# jayday.net
KiCad netlist of a schematic drawn in EAGLE
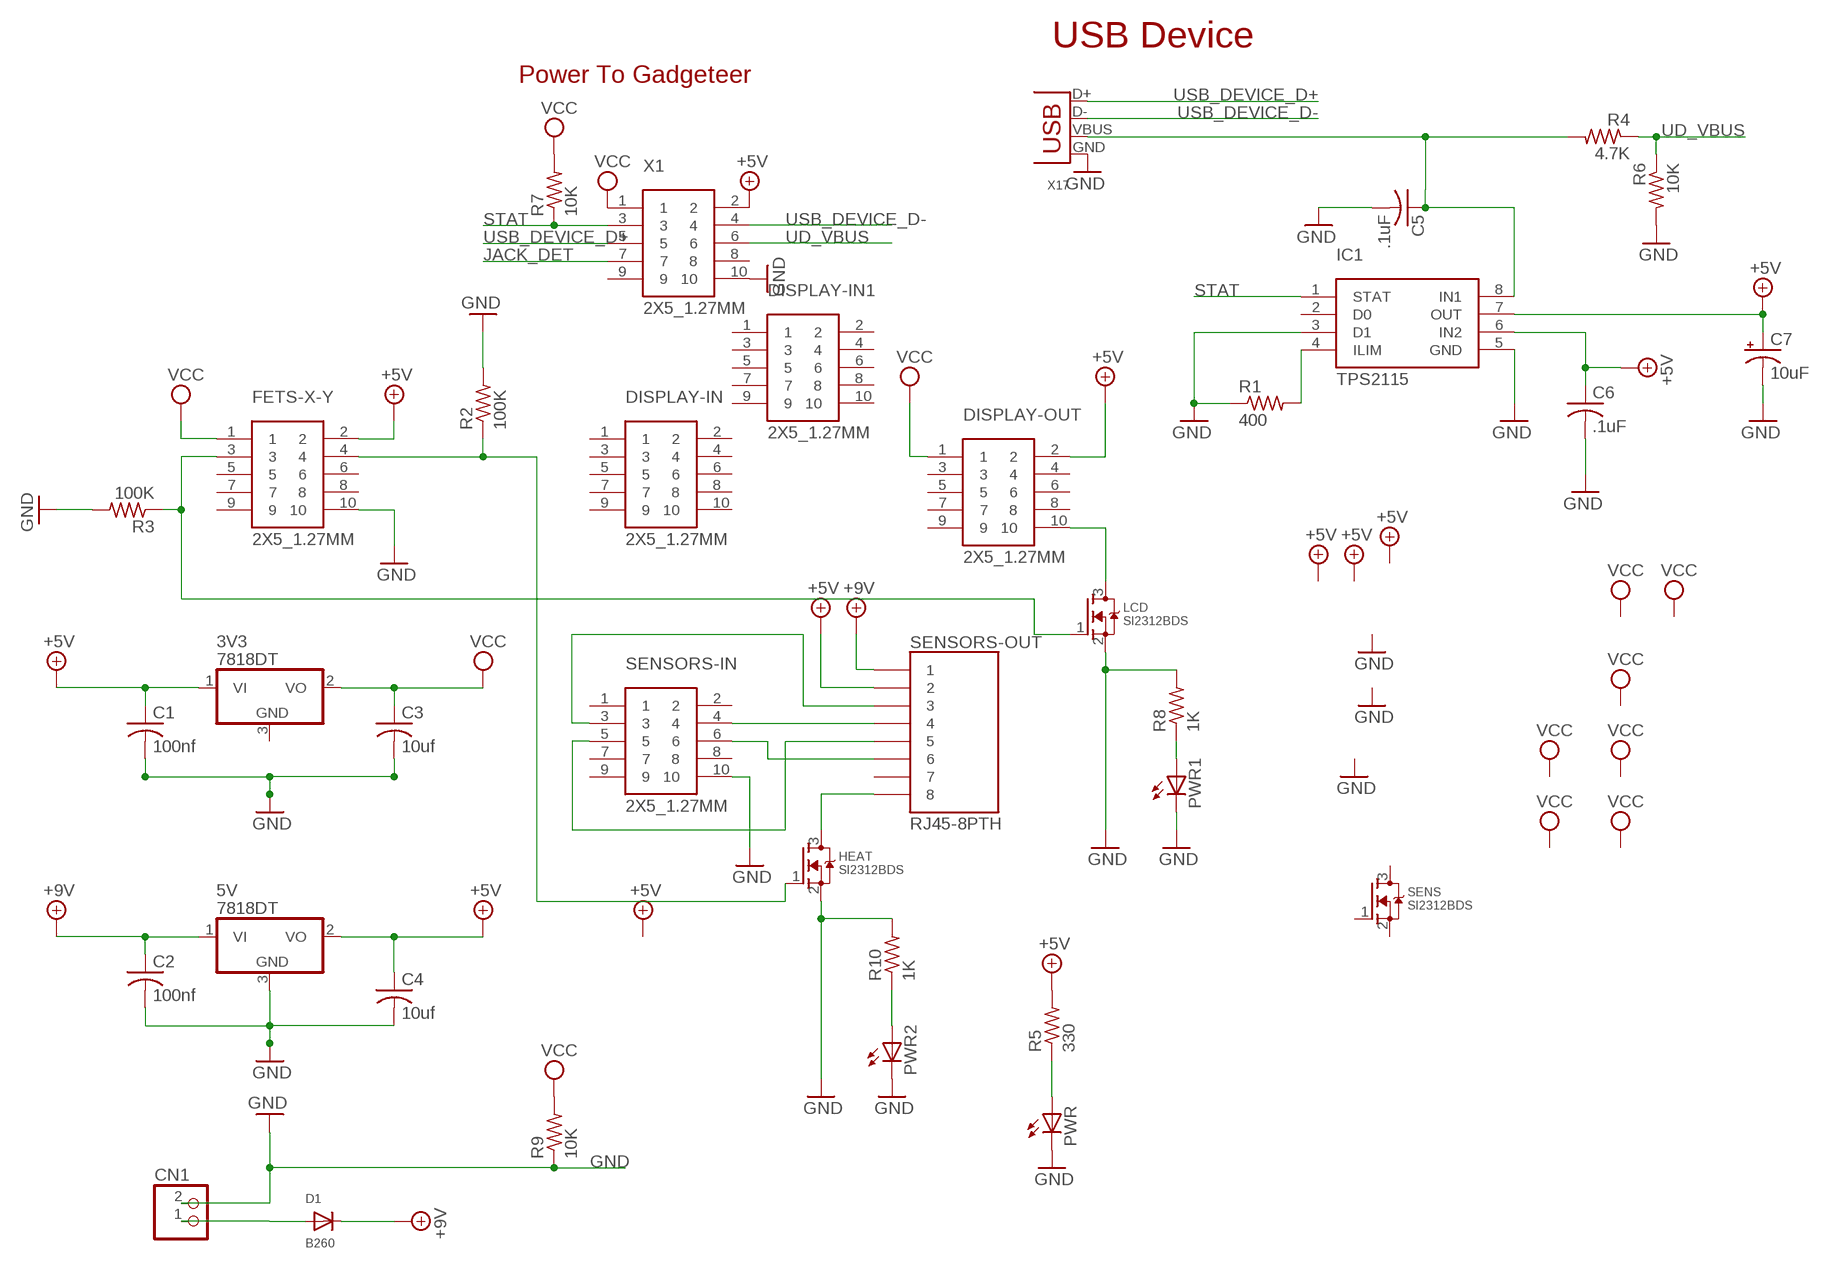
[diagram p0: schematic, sheet 1]

(export (version "E")
  (design (tool "Eeschema 10.0.6"))
  (components
    (comp (ref "3V3")
      (value "7818DT")
      (footprint "eagle-import:TO252")
      (libsource (lib "eagle-import") (part "78DT18"))
    )
    (comp (ref "5V")
      (value "7818DT")
      (footprint "eagle-import:TO252")
      (libsource (lib "eagle-import") (part "78DT18"))
    )
    (comp (ref "C1")
      (value "100nf")
      (footprint "eagle-import:C0805")
      (libsource (lib "eagle-import") (part "C-USC0805"))
    )
    (comp (ref "C2")
      (value "100nf")
      (footprint "eagle-import:C0805")
      (libsource (lib "eagle-import") (part "C-USC0805"))
    )
    (comp (ref "C3")
      (value "10uf")
      (footprint "eagle-import:C0805")
      (libsource (lib "eagle-import") (part "C-USC0805"))
    )
    (comp (ref "C4")
      (value "10uf")
      (footprint "eagle-import:C0805")
      (libsource (lib "eagle-import") (part "C-USC0805"))
    )
    (comp (ref "C5")
      (value ".1uF")
      (footprint "eagle-import:C0603K")
      (libsource (lib "eagle-import") (part "rcl_C-USC0603K"))
    )
    (comp (ref "C6")
      (value ".1uF")
      (footprint "eagle-import:C0603K")
      (libsource (lib "eagle-import") (part "rcl_C-USC0603K"))
    )
    (comp (ref "C7")
      (value "10uF")
      (footprint "eagle-import:CT3528")
      (libsource (lib "eagle-import") (part "CPOL-USCT3528"))
    )
    (comp (ref "CN1")
      (value "JST_2PIN-THM-RA")
      (footprint "eagle-import:JST-PH-2-THM-RA")
      (libsource (lib "eagle-import") (part "JST_2PIN-THM-RA"))
    )
    (comp (ref "D1")
      (value "B260")
      (footprint "eagle-import:SMADIODE")
      (libsource (lib "eagle-import") (part "DIODESMA"))
    )
    (comp (ref "DISPLAY-IN")
      (value "2X5_1.27MM")
      (footprint "eagle-import:2X5_1.27MM")
      (libsource (lib "eagle-import") (part "2X5_1.27MM"))
    )
    (comp (ref "DISPLAY-IN1")
      (value "2X5_1.27MM")
      (footprint "eagle-import:2X5_1.27MM")
      (libsource (lib "eagle-import") (part "2X5_1.27MM"))
    )
    (comp (ref "DISPLAY-OUT")
      (value "2X5_1.27MM")
      (footprint "eagle-import:2X5_1.27MM")
      (libsource (lib "eagle-import") (part "2X5_1.27MM"))
    )
    (comp (ref "FETS-X-Y")
      (value "2X5_1.27MM")
      (footprint "eagle-import:2X5_1.27MM")
      (libsource (lib "eagle-import") (part "2X5_1.27MM"))
    )
    (comp (ref "HEAT")
      (value "SI2312BDS")
      (footprint "eagle-import:TO-236")
      (libsource (lib "eagle-import") (part "SI2312BDS"))
    )
    (comp (ref "IC1")
      (value "TPS2115")
      (footprint "eagle-import:TSSOP8")
      (libsource (lib "eagle-import") (part "TSP2115"))
    )
    (comp (ref "LCD")
      (value "SI2312BDS")
      (footprint "eagle-import:TO-236")
      (libsource (lib "eagle-import") (part "SI2312BDS"))
    )
    (comp (ref "PWR")
      (value "LEDCHIPLED_0805")
      (footprint "eagle-import:CHIPLED_0805")
      (libsource (lib "eagle-import") (part "LEDCHIPLED_0805"))
    )
    (comp (ref "PWR1")
      (value "LEDCHIPLED_0805")
      (footprint "eagle-import:CHIPLED_0805")
      (libsource (lib "eagle-import") (part "LEDCHIPLED_0805"))
    )
    (comp (ref "PWR2")
      (value "LEDCHIPLED_0805")
      (footprint "eagle-import:CHIPLED_0805")
      (libsource (lib "eagle-import") (part "LEDCHIPLED_0805"))
    )
    (comp (ref "R1")
      (value "400")
      (footprint "eagle-import:R0603")
      (libsource (lib "eagle-import") (part "R-US_R0603"))
    )
    (comp (ref "R2")
      (value "100K")
      (footprint "eagle-import:R0603")
      (libsource (lib "eagle-import") (part "R-US_R0603"))
    )
    (comp (ref "R3")
      (value "100K")
      (footprint "eagle-import:R0603")
      (libsource (lib "eagle-import") (part "R-US_R0603"))
    )
    (comp (ref "R4")
      (value "4.7K")
      (footprint "eagle-import:R0603")
      (libsource (lib "eagle-import") (part "R-US_R0603"))
    )
    (comp (ref "R5")
      (value "330")
      (footprint "eagle-import:R0603")
      (libsource (lib "eagle-import") (part "R-US_R0603"))
    )
    (comp (ref "R6")
      (value "10K")
      (footprint "eagle-import:R0603")
      (libsource (lib "eagle-import") (part "R-US_R0603"))
    )
    (comp (ref "R7")
      (value "10K")
      (footprint "eagle-import:R0603")
      (libsource (lib "eagle-import") (part "R-US_R0603"))
    )
    (comp (ref "R8")
      (value "1K")
      (footprint "eagle-import:R0603")
      (libsource (lib "eagle-import") (part "R-US_R0603"))
    )
    (comp (ref "R9")
      (value "10K")
      (footprint "eagle-import:R0603")
      (libsource (lib "eagle-import") (part "R-US_R0603"))
    )
    (comp (ref "R10")
      (value "1K")
      (footprint "eagle-import:R0603")
      (libsource (lib "eagle-import") (part "R-US_R0603"))
    )
    (comp (ref "SENS")
      (value "SI2312BDS")
      (footprint "eagle-import:TO-236")
      (libsource (lib "eagle-import") (part "SI2312BDS"))
    )
    (comp (ref "SENSORS-IN")
      (value "2X5_1.27MM")
      (footprint "eagle-import:2X5_1.27MM")
      (libsource (lib "eagle-import") (part "2X5_1.27MM"))
    )
    (comp (ref "SENSORS-OUT")
      (value "RJ45-8PTH")
      (footprint "eagle-import:RJ45-8")
      (libsource (lib "eagle-import") (part "RJ45-8PTH"))
    )
    (comp (ref "X1")
      (value "2X5_1.27MM")
      (footprint "eagle-import:2X5_1.27MM")
      (libsource (lib "eagle-import") (part "2X5_1.27MM"))
    )
    (comp (ref "X17")
      (value "DX2R005HN2E700")
      (footprint "eagle-import:USB-MB-S")
      (libsource (lib "eagle-import") (part "USB-MB-S"))
    )
  )
  (nets
    (net (code "1") (name "+5V") (class "Default")
      (node (ref "3V3") (pin "1") (pinfunction "VI_1") (pintype "input"))
      (node (ref "5V") (pin "2") (pinfunction "VO_2") (pintype "passive"))
      (node (ref "C1") (pin "1") (pinfunction "1_1") (pintype "passive"))
      (node (ref "C4") (pin "1") (pinfunction "1_1") (pintype "passive"))
      (node (ref "C6") (pin "1") (pinfunction "1_1") (pintype "passive"))
      (node (ref "C7") (pin "+") (pinfunction "+_+") (pintype "passive"))
      (node (ref "DISPLAY-OUT") (pin "2") (pinfunction "2_2") (pintype "bidirectional"))
      (node (ref "FETS-X-Y") (pin "2") (pinfunction "2_2") (pintype "bidirectional"))
      (node (ref "IC1") (pin "6") (pinfunction "IN2_6") (pintype "bidirectional"))
      (node (ref "IC1") (pin "7") (pinfunction "OUT_7") (pintype "bidirectional"))
      (node (ref "R5") (pin "2") (pinfunction "2_2") (pintype "passive"))
      (node (ref "SENSORS-OUT") (pin "2") (pinfunction "2_2") (pintype "bidirectional"))
      (node (ref "X1") (pin "2") (pinfunction "2_2") (pintype "bidirectional"))
    )
    (net (code "2") (name "+9V") (class "Default")
      (node (ref "5V") (pin "1") (pinfunction "VI_1") (pintype "input"))
      (node (ref "C2") (pin "1") (pinfunction "1_1") (pintype "passive"))
      (node (ref "D1") (pin "C") (pinfunction "C_C") (pintype "passive"))
      (node (ref "SENSORS-OUT") (pin "1") (pinfunction "1_1") (pintype "bidirectional"))
    )
    (net (code "3") (name "/JACK_DET") (class "Default")
      (node (ref "X1") (pin "7") (pinfunction "7_7") (pintype "bidirectional"))
    )
    (net (code "4") (name "/STAT") (class "Default")
      (node (ref "IC1") (pin "1") (pinfunction "STAT_1") (pintype "bidirectional"))
      (node (ref "R7") (pin "1") (pinfunction "1_1") (pintype "passive"))
      (node (ref "X1") (pin "3") (pinfunction "3_3") (pintype "bidirectional"))
    )
    (net (code "5") (name "/UD_VBUS") (class "Default")
      (node (ref "R4") (pin "1") (pinfunction "1_1") (pintype "passive"))
      (node (ref "R6") (pin "1") (pinfunction "1_1") (pintype "passive"))
      (node (ref "X1") (pin "6") (pinfunction "6_6") (pintype "bidirectional"))
    )
    (net (code "6") (name "/USB_DEVICE_D+") (class "Default")
      (node (ref "X1") (pin "5") (pinfunction "5_5") (pintype "bidirectional"))
      (node (ref "X17") (pin "D+") (pinfunction "D+_D+") (pintype "bidirectional"))
    )
    (net (code "7") (name "/USB_DEVICE_D-") (class "Default")
      (node (ref "X1") (pin "4") (pinfunction "4_4") (pintype "bidirectional"))
      (node (ref "X17") (pin "D-") (pinfunction "D-_D-") (pintype "bidirectional"))
    )
    (net (code "8") (name "GND") (class "Default")
      (node (ref "5V") (pin "3") (pinfunction "GND_3") (pintype "passive"))
      (node (ref "C1") (pin "2") (pinfunction "2_2") (pintype "passive"))
      (node (ref "C2") (pin "2") (pinfunction "2_2") (pintype "passive"))
      (node (ref "C3") (pin "2") (pinfunction "2_2") (pintype "passive"))
      (node (ref "C4") (pin "2") (pinfunction "2_2") (pintype "passive"))
      (node (ref "C5") (pin "2") (pinfunction "2_2") (pintype "passive"))
      (node (ref "C6") (pin "2") (pinfunction "2_2") (pintype "passive"))
      (node (ref "C7") (pin "-") (pinfunction "-_-") (pintype "passive"))
      (node (ref "CN1") (pin "2") (pinfunction "1_2") (pintype "passive"))
      (node (ref "FETS-X-Y") (pin "10") (pinfunction "10_10") (pintype "bidirectional"))
      (node (ref "HEAT") (pin "2") (pinfunction "S_2") (pintype "bidirectional"))
      (node (ref "IC1") (pin "3") (pinfunction "D1_3") (pintype "bidirectional"))
      (node (ref "IC1") (pin "5") (pinfunction "GND_5") (pintype "bidirectional"))
      (node (ref "LCD") (pin "2") (pinfunction "S_2") (pintype "bidirectional"))
      (node (ref "PWR") (pin "C") (pinfunction "C_C") (pintype "passive"))
      (node (ref "PWR1") (pin "C") (pinfunction "C_C") (pintype "passive"))
      (node (ref "PWR2") (pin "C") (pinfunction "C_C") (pintype "passive"))
      (node (ref "R1") (pin "1") (pinfunction "1_1") (pintype "passive"))
      (node (ref "R10") (pin "2") (pinfunction "2_2") (pintype "passive"))
      (node (ref "R2") (pin "2") (pinfunction "2_2") (pintype "passive"))
      (node (ref "R3") (pin "2") (pinfunction "2_2") (pintype "passive"))
      (node (ref "R6") (pin "2") (pinfunction "2_2") (pintype "passive"))
      (node (ref "R8") (pin "2") (pinfunction "2_2") (pintype "passive"))
      (node (ref "R9") (pin "1") (pinfunction "1_1") (pintype "passive"))
      (node (ref "SENSORS-IN") (pin "10") (pinfunction "10_10") (pintype "bidirectional"))
      (node (ref "X1") (pin "10") (pinfunction "10_10") (pintype "bidirectional"))
      (node (ref "X17") (pin "GND") (pinfunction "GND_GND") (pintype "bidirectional"))
    )
    (net (code "9") (name "Net-(CN1-2)") (class "Default")
      (node (ref "CN1") (pin "1") (pinfunction "2_1") (pintype "passive"))
      (node (ref "D1") (pin "A") (pinfunction "A_A") (pintype "passive"))
    )
    (net (code "10") (name "Net-(HEAT-D)") (class "Default")
      (node (ref "HEAT") (pin "3") (pinfunction "D_3") (pintype "bidirectional"))
      (node (ref "SENSORS-OUT") (pin "8") (pinfunction "8_8") (pintype "bidirectional"))
    )
    (net (code "11") (name "Net-(HEAT-G)") (class "Default")
      (node (ref "FETS-X-Y") (pin "4") (pinfunction "4_4") (pintype "bidirectional"))
      (node (ref "HEAT") (pin "1") (pinfunction "G_1") (pintype "bidirectional"))
      (node (ref "R2") (pin "1") (pinfunction "1_1") (pintype "passive"))
    )
    (net (code "12") (name "Net-(IC1-ILIM)") (class "Default")
      (node (ref "IC1") (pin "4") (pinfunction "ILIM_4") (pintype "bidirectional"))
      (node (ref "R1") (pin "2") (pinfunction "2_2") (pintype "passive"))
    )
    (net (code "13") (name "Net-(IC1-IN1)") (class "Default")
      (node (ref "C5") (pin "1") (pinfunction "1_1") (pintype "passive"))
      (node (ref "IC1") (pin "8") (pinfunction "IN1_8") (pintype "bidirectional"))
      (node (ref "R4") (pin "2") (pinfunction "2_2") (pintype "passive"))
      (node (ref "X17") (pin "VBUS") (pinfunction "VBUS_VBUS") (pintype "bidirectional"))
    )
    (net (code "14") (name "Net-(LCD-D)") (class "Default")
      (node (ref "DISPLAY-OUT") (pin "10") (pinfunction "10_10") (pintype "bidirectional"))
      (node (ref "LCD") (pin "3") (pinfunction "D_3") (pintype "bidirectional"))
    )
    (net (code "15") (name "Net-(LCD-G)") (class "Default")
      (node (ref "FETS-X-Y") (pin "3") (pinfunction "3_3") (pintype "bidirectional"))
      (node (ref "LCD") (pin "1") (pinfunction "G_1") (pintype "bidirectional"))
      (node (ref "R3") (pin "1") (pinfunction "1_1") (pintype "passive"))
    )
    (net (code "16") (name "Net-(PWR-PadA)") (class "Default")
      (node (ref "PWR") (pin "A") (pinfunction "A_A") (pintype "passive"))
      (node (ref "R5") (pin "1") (pinfunction "1_1") (pintype "passive"))
    )
    (net (code "17") (name "Net-(PWR1-PadA)") (class "Default")
      (node (ref "PWR1") (pin "A") (pinfunction "A_A") (pintype "passive"))
      (node (ref "R8") (pin "1") (pinfunction "1_1") (pintype "passive"))
    )
    (net (code "18") (name "Net-(PWR2-PadA)") (class "Default")
      (node (ref "PWR2") (pin "A") (pinfunction "A_A") (pintype "passive"))
      (node (ref "R10") (pin "1") (pinfunction "1_1") (pintype "passive"))
    )
    (net (code "19") (name "Net-(SENSORS-IN-Pad3)") (class "Default")
      (node (ref "SENSORS-IN") (pin "3") (pinfunction "3_3") (pintype "bidirectional"))
      (node (ref "SENSORS-OUT") (pin "3") (pinfunction "3_3") (pintype "bidirectional"))
    )
    (net (code "20") (name "Net-(SENSORS-IN-Pad4)") (class "Default")
      (node (ref "SENSORS-IN") (pin "4") (pinfunction "4_4") (pintype "bidirectional"))
      (node (ref "SENSORS-OUT") (pin "4") (pinfunction "4_4") (pintype "bidirectional"))
    )
    (net (code "21") (name "Net-(SENSORS-IN-Pad5)") (class "Default")
      (node (ref "SENSORS-IN") (pin "5") (pinfunction "5_5") (pintype "bidirectional"))
      (node (ref "SENSORS-OUT") (pin "5") (pinfunction "5_5") (pintype "bidirectional"))
    )
    (net (code "22") (name "Net-(SENSORS-IN-Pad6)") (class "Default")
      (node (ref "SENSORS-IN") (pin "6") (pinfunction "6_6") (pintype "bidirectional"))
      (node (ref "SENSORS-OUT") (pin "6") (pinfunction "6_6") (pintype "bidirectional"))
    )
    (net (code "23") (name "VCC") (class "Default")
      (node (ref "3V3") (pin "2") (pinfunction "VO_2") (pintype "passive"))
      (node (ref "C3") (pin "1") (pinfunction "1_1") (pintype "passive"))
      (node (ref "DISPLAY-OUT") (pin "1") (pinfunction "1_1") (pintype "bidirectional"))
      (node (ref "FETS-X-Y") (pin "1") (pinfunction "1_1") (pintype "bidirectional"))
      (node (ref "R7") (pin "2") (pinfunction "2_2") (pintype "passive"))
      (node (ref "R9") (pin "2") (pinfunction "2_2") (pintype "passive"))
      (node (ref "X1") (pin "1") (pinfunction "1_1") (pintype "bidirectional"))
    )
    (net (code "24") (name "unconnected-(3V3-GND-Pad3)") (class "Default")
      (node (ref "3V3") (pin "3") (pinfunction "GND_3") (pintype "passive"))
    )
    (net (code "25") (name "unconnected-(DISPLAY-IN-Pad1)") (class "Default")
      (node (ref "DISPLAY-IN") (pin "1") (pinfunction "1_1") (pintype "bidirectional"))
    )
    (net (code "26") (name "unconnected-(DISPLAY-IN-Pad2)") (class "Default")
      (node (ref "DISPLAY-IN") (pin "2") (pinfunction "2_2") (pintype "bidirectional"))
    )
    (net (code "27") (name "unconnected-(DISPLAY-IN-Pad3)") (class "Default")
      (node (ref "DISPLAY-IN") (pin "3") (pinfunction "3_3") (pintype "bidirectional"))
    )
    (net (code "28") (name "unconnected-(DISPLAY-IN-Pad4)") (class "Default")
      (node (ref "DISPLAY-IN") (pin "4") (pinfunction "4_4") (pintype "bidirectional"))
    )
    (net (code "29") (name "unconnected-(DISPLAY-IN-Pad5)") (class "Default")
      (node (ref "DISPLAY-IN") (pin "5") (pinfunction "5_5") (pintype "bidirectional"))
    )
    (net (code "30") (name "unconnected-(DISPLAY-IN-Pad6)") (class "Default")
      (node (ref "DISPLAY-IN") (pin "6") (pinfunction "6_6") (pintype "bidirectional"))
    )
    (net (code "31") (name "unconnected-(DISPLAY-IN-Pad7)") (class "Default")
      (node (ref "DISPLAY-IN") (pin "7") (pinfunction "7_7") (pintype "bidirectional"))
    )
    (net (code "32") (name "unconnected-(DISPLAY-IN-Pad8)") (class "Default")
      (node (ref "DISPLAY-IN") (pin "8") (pinfunction "8_8") (pintype "bidirectional"))
    )
    (net (code "33") (name "unconnected-(DISPLAY-IN-Pad9)") (class "Default")
      (node (ref "DISPLAY-IN") (pin "9") (pinfunction "9_9") (pintype "bidirectional"))
    )
    (net (code "34") (name "unconnected-(DISPLAY-IN-Pad10)") (class "Default")
      (node (ref "DISPLAY-IN") (pin "10") (pinfunction "10_10") (pintype "bidirectional"))
    )
    (net (code "35") (name "unconnected-(DISPLAY-IN1-Pad1)") (class "Default")
      (node (ref "DISPLAY-IN1") (pin "1") (pinfunction "1_1") (pintype "bidirectional"))
    )
    (net (code "36") (name "unconnected-(DISPLAY-IN1-Pad2)") (class "Default")
      (node (ref "DISPLAY-IN1") (pin "2") (pinfunction "2_2") (pintype "bidirectional"))
    )
    (net (code "37") (name "unconnected-(DISPLAY-IN1-Pad3)") (class "Default")
      (node (ref "DISPLAY-IN1") (pin "3") (pinfunction "3_3") (pintype "bidirectional"))
    )
    (net (code "38") (name "unconnected-(DISPLAY-IN1-Pad4)") (class "Default")
      (node (ref "DISPLAY-IN1") (pin "4") (pinfunction "4_4") (pintype "bidirectional"))
    )
    (net (code "39") (name "unconnected-(DISPLAY-IN1-Pad5)") (class "Default")
      (node (ref "DISPLAY-IN1") (pin "5") (pinfunction "5_5") (pintype "bidirectional"))
    )
    (net (code "40") (name "unconnected-(DISPLAY-IN1-Pad6)") (class "Default")
      (node (ref "DISPLAY-IN1") (pin "6") (pinfunction "6_6") (pintype "bidirectional"))
    )
    (net (code "41") (name "unconnected-(DISPLAY-IN1-Pad7)") (class "Default")
      (node (ref "DISPLAY-IN1") (pin "7") (pinfunction "7_7") (pintype "bidirectional"))
    )
    (net (code "42") (name "unconnected-(DISPLAY-IN1-Pad8)") (class "Default")
      (node (ref "DISPLAY-IN1") (pin "8") (pinfunction "8_8") (pintype "bidirectional"))
    )
    (net (code "43") (name "unconnected-(DISPLAY-IN1-Pad9)") (class "Default")
      (node (ref "DISPLAY-IN1") (pin "9") (pinfunction "9_9") (pintype "bidirectional"))
    )
    (net (code "44") (name "unconnected-(DISPLAY-IN1-Pad10)") (class "Default")
      (node (ref "DISPLAY-IN1") (pin "10") (pinfunction "10_10") (pintype "bidirectional"))
    )
    (net (code "45") (name "unconnected-(DISPLAY-OUT-Pad3)") (class "Default")
      (node (ref "DISPLAY-OUT") (pin "3") (pinfunction "3_3") (pintype "bidirectional"))
    )
    (net (code "46") (name "unconnected-(DISPLAY-OUT-Pad4)") (class "Default")
      (node (ref "DISPLAY-OUT") (pin "4") (pinfunction "4_4") (pintype "bidirectional"))
    )
    (net (code "47") (name "unconnected-(DISPLAY-OUT-Pad5)") (class "Default")
      (node (ref "DISPLAY-OUT") (pin "5") (pinfunction "5_5") (pintype "bidirectional"))
    )
    (net (code "48") (name "unconnected-(DISPLAY-OUT-Pad6)") (class "Default")
      (node (ref "DISPLAY-OUT") (pin "6") (pinfunction "6_6") (pintype "bidirectional"))
    )
    (net (code "49") (name "unconnected-(DISPLAY-OUT-Pad7)") (class "Default")
      (node (ref "DISPLAY-OUT") (pin "7") (pinfunction "7_7") (pintype "bidirectional"))
    )
    (net (code "50") (name "unconnected-(DISPLAY-OUT-Pad8)") (class "Default")
      (node (ref "DISPLAY-OUT") (pin "8") (pinfunction "8_8") (pintype "bidirectional"))
    )
    (net (code "51") (name "unconnected-(DISPLAY-OUT-Pad9)") (class "Default")
      (node (ref "DISPLAY-OUT") (pin "9") (pinfunction "9_9") (pintype "bidirectional"))
    )
    (net (code "52") (name "unconnected-(FETS-X-Y-Pad5)") (class "Default")
      (node (ref "FETS-X-Y") (pin "5") (pinfunction "5_5") (pintype "bidirectional"))
    )
    (net (code "53") (name "unconnected-(FETS-X-Y-Pad6)") (class "Default")
      (node (ref "FETS-X-Y") (pin "6") (pinfunction "6_6") (pintype "bidirectional"))
    )
    (net (code "54") (name "unconnected-(FETS-X-Y-Pad7)") (class "Default")
      (node (ref "FETS-X-Y") (pin "7") (pinfunction "7_7") (pintype "bidirectional"))
    )
    (net (code "55") (name "unconnected-(FETS-X-Y-Pad8)") (class "Default")
      (node (ref "FETS-X-Y") (pin "8") (pinfunction "8_8") (pintype "bidirectional"))
    )
    (net (code "56") (name "unconnected-(FETS-X-Y-Pad9)") (class "Default")
      (node (ref "FETS-X-Y") (pin "9") (pinfunction "9_9") (pintype "bidirectional"))
    )
    (net (code "57") (name "unconnected-(IC1-D0-Pad2)") (class "Default")
      (node (ref "IC1") (pin "2") (pinfunction "D0_2") (pintype "bidirectional"))
    )
    (net (code "58") (name "unconnected-(SENS-D-Pad3)") (class "Default")
      (node (ref "SENS") (pin "3") (pinfunction "D_3") (pintype "bidirectional"))
    )
    (net (code "59") (name "unconnected-(SENS-G-Pad1)") (class "Default")
      (node (ref "SENS") (pin "1") (pinfunction "G_1") (pintype "bidirectional"))
    )
    (net (code "60") (name "unconnected-(SENS-S-Pad2)") (class "Default")
      (node (ref "SENS") (pin "2") (pinfunction "S_2") (pintype "bidirectional"))
    )
    (net (code "61") (name "unconnected-(SENSORS-IN-Pad1)") (class "Default")
      (node (ref "SENSORS-IN") (pin "1") (pinfunction "1_1") (pintype "bidirectional"))
    )
    (net (code "62") (name "unconnected-(SENSORS-IN-Pad2)") (class "Default")
      (node (ref "SENSORS-IN") (pin "2") (pinfunction "2_2") (pintype "bidirectional"))
    )
    (net (code "63") (name "unconnected-(SENSORS-IN-Pad7)") (class "Default")
      (node (ref "SENSORS-IN") (pin "7") (pinfunction "7_7") (pintype "bidirectional"))
    )
    (net (code "64") (name "unconnected-(SENSORS-IN-Pad8)") (class "Default")
      (node (ref "SENSORS-IN") (pin "8") (pinfunction "8_8") (pintype "bidirectional"))
    )
    (net (code "65") (name "unconnected-(SENSORS-IN-Pad9)") (class "Default")
      (node (ref "SENSORS-IN") (pin "9") (pinfunction "9_9") (pintype "bidirectional"))
    )
    (net (code "66") (name "unconnected-(SENSORS-OUT-Pad7)") (class "Default")
      (node (ref "SENSORS-OUT") (pin "7") (pinfunction "7_7") (pintype "bidirectional"))
    )
    (net (code "67") (name "unconnected-(X1-Pad8)") (class "Default")
      (node (ref "X1") (pin "8") (pinfunction "8_8") (pintype "bidirectional"))
    )
    (net (code "68") (name "unconnected-(X1-Pad9)") (class "Default")
      (node (ref "X1") (pin "9") (pinfunction "9_9") (pintype "bidirectional"))
    )
  )
)
